# Clock_Display.net
KiCad netlist of a schematic drawn in EAGLE
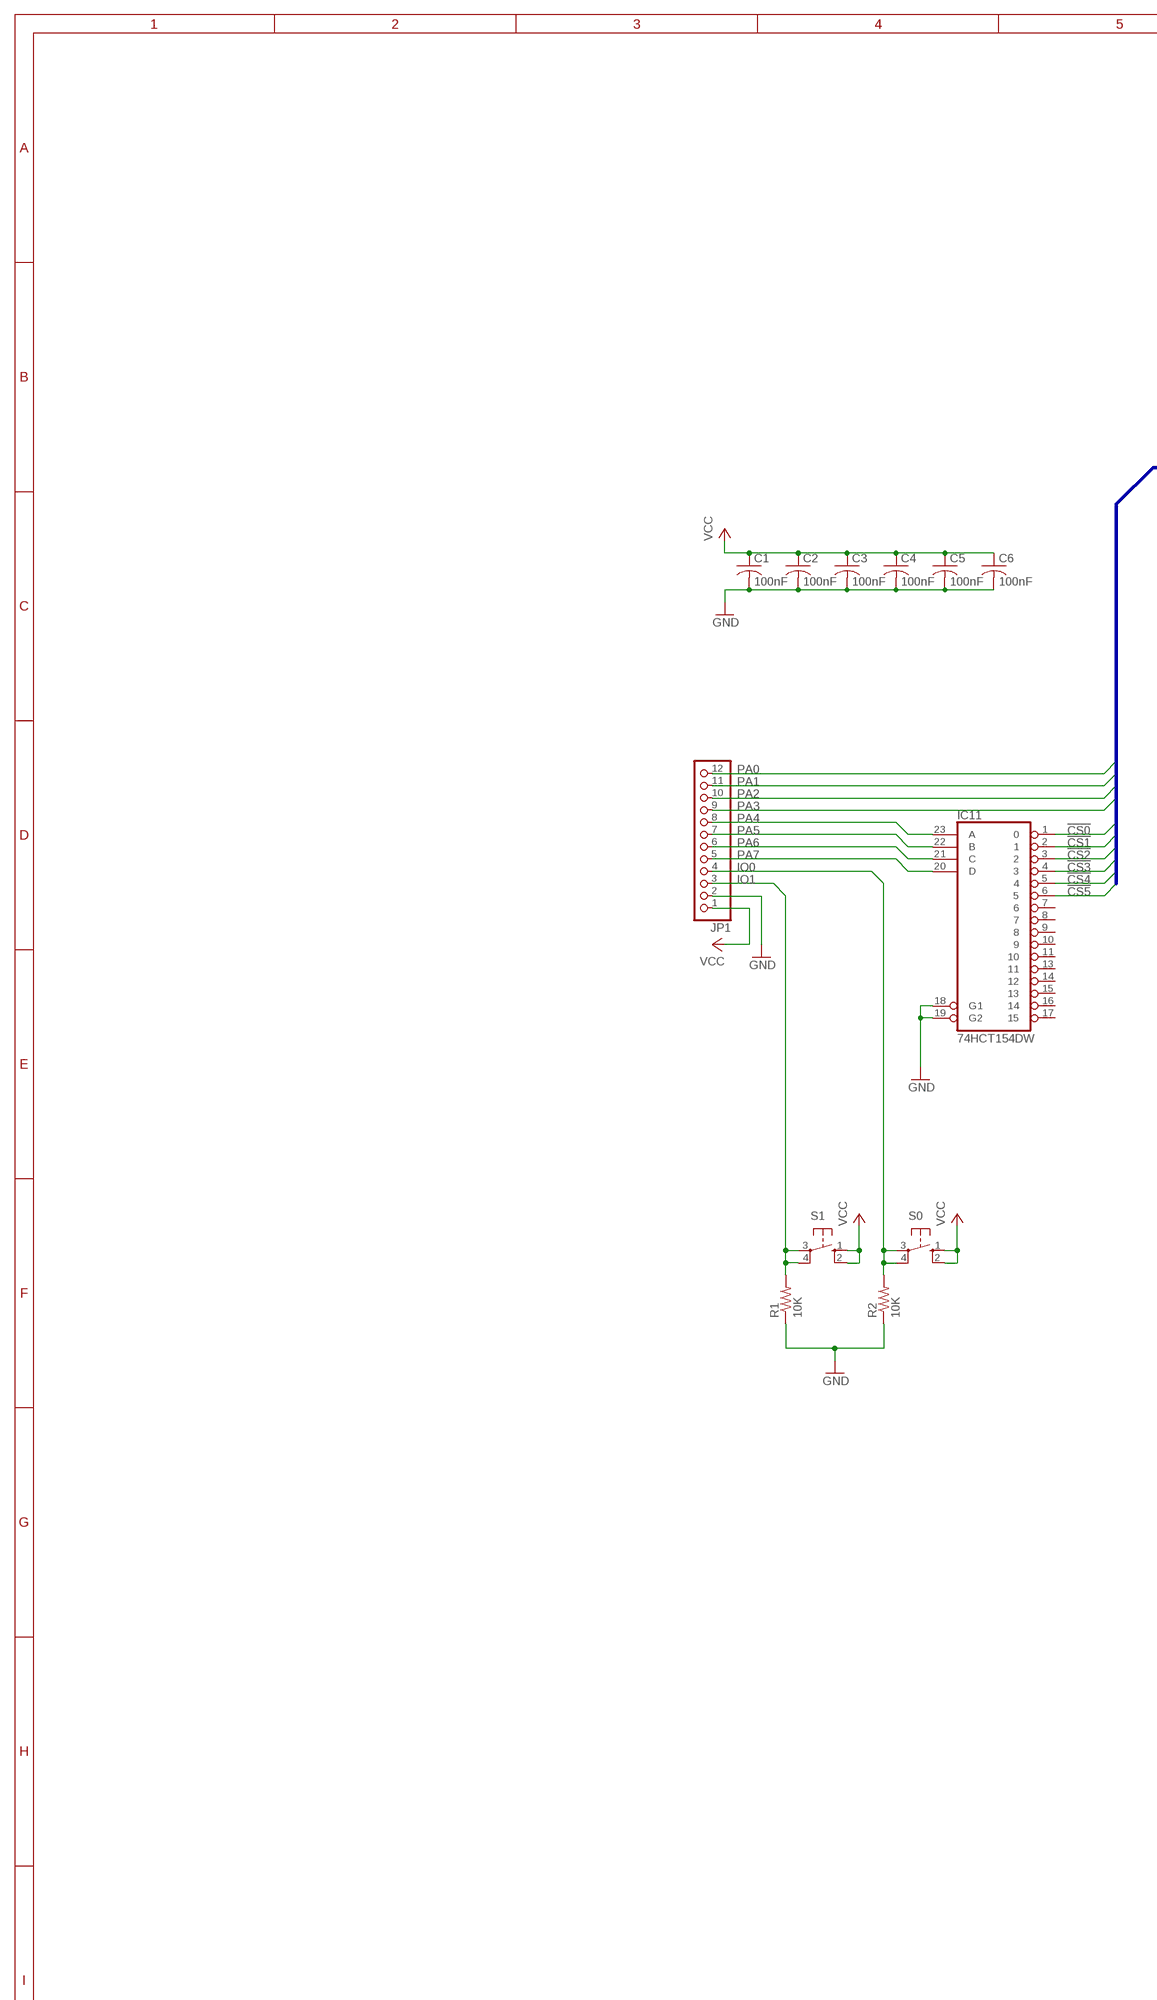
[diagram p0: schematic, sheet 1, part 1 of 2]
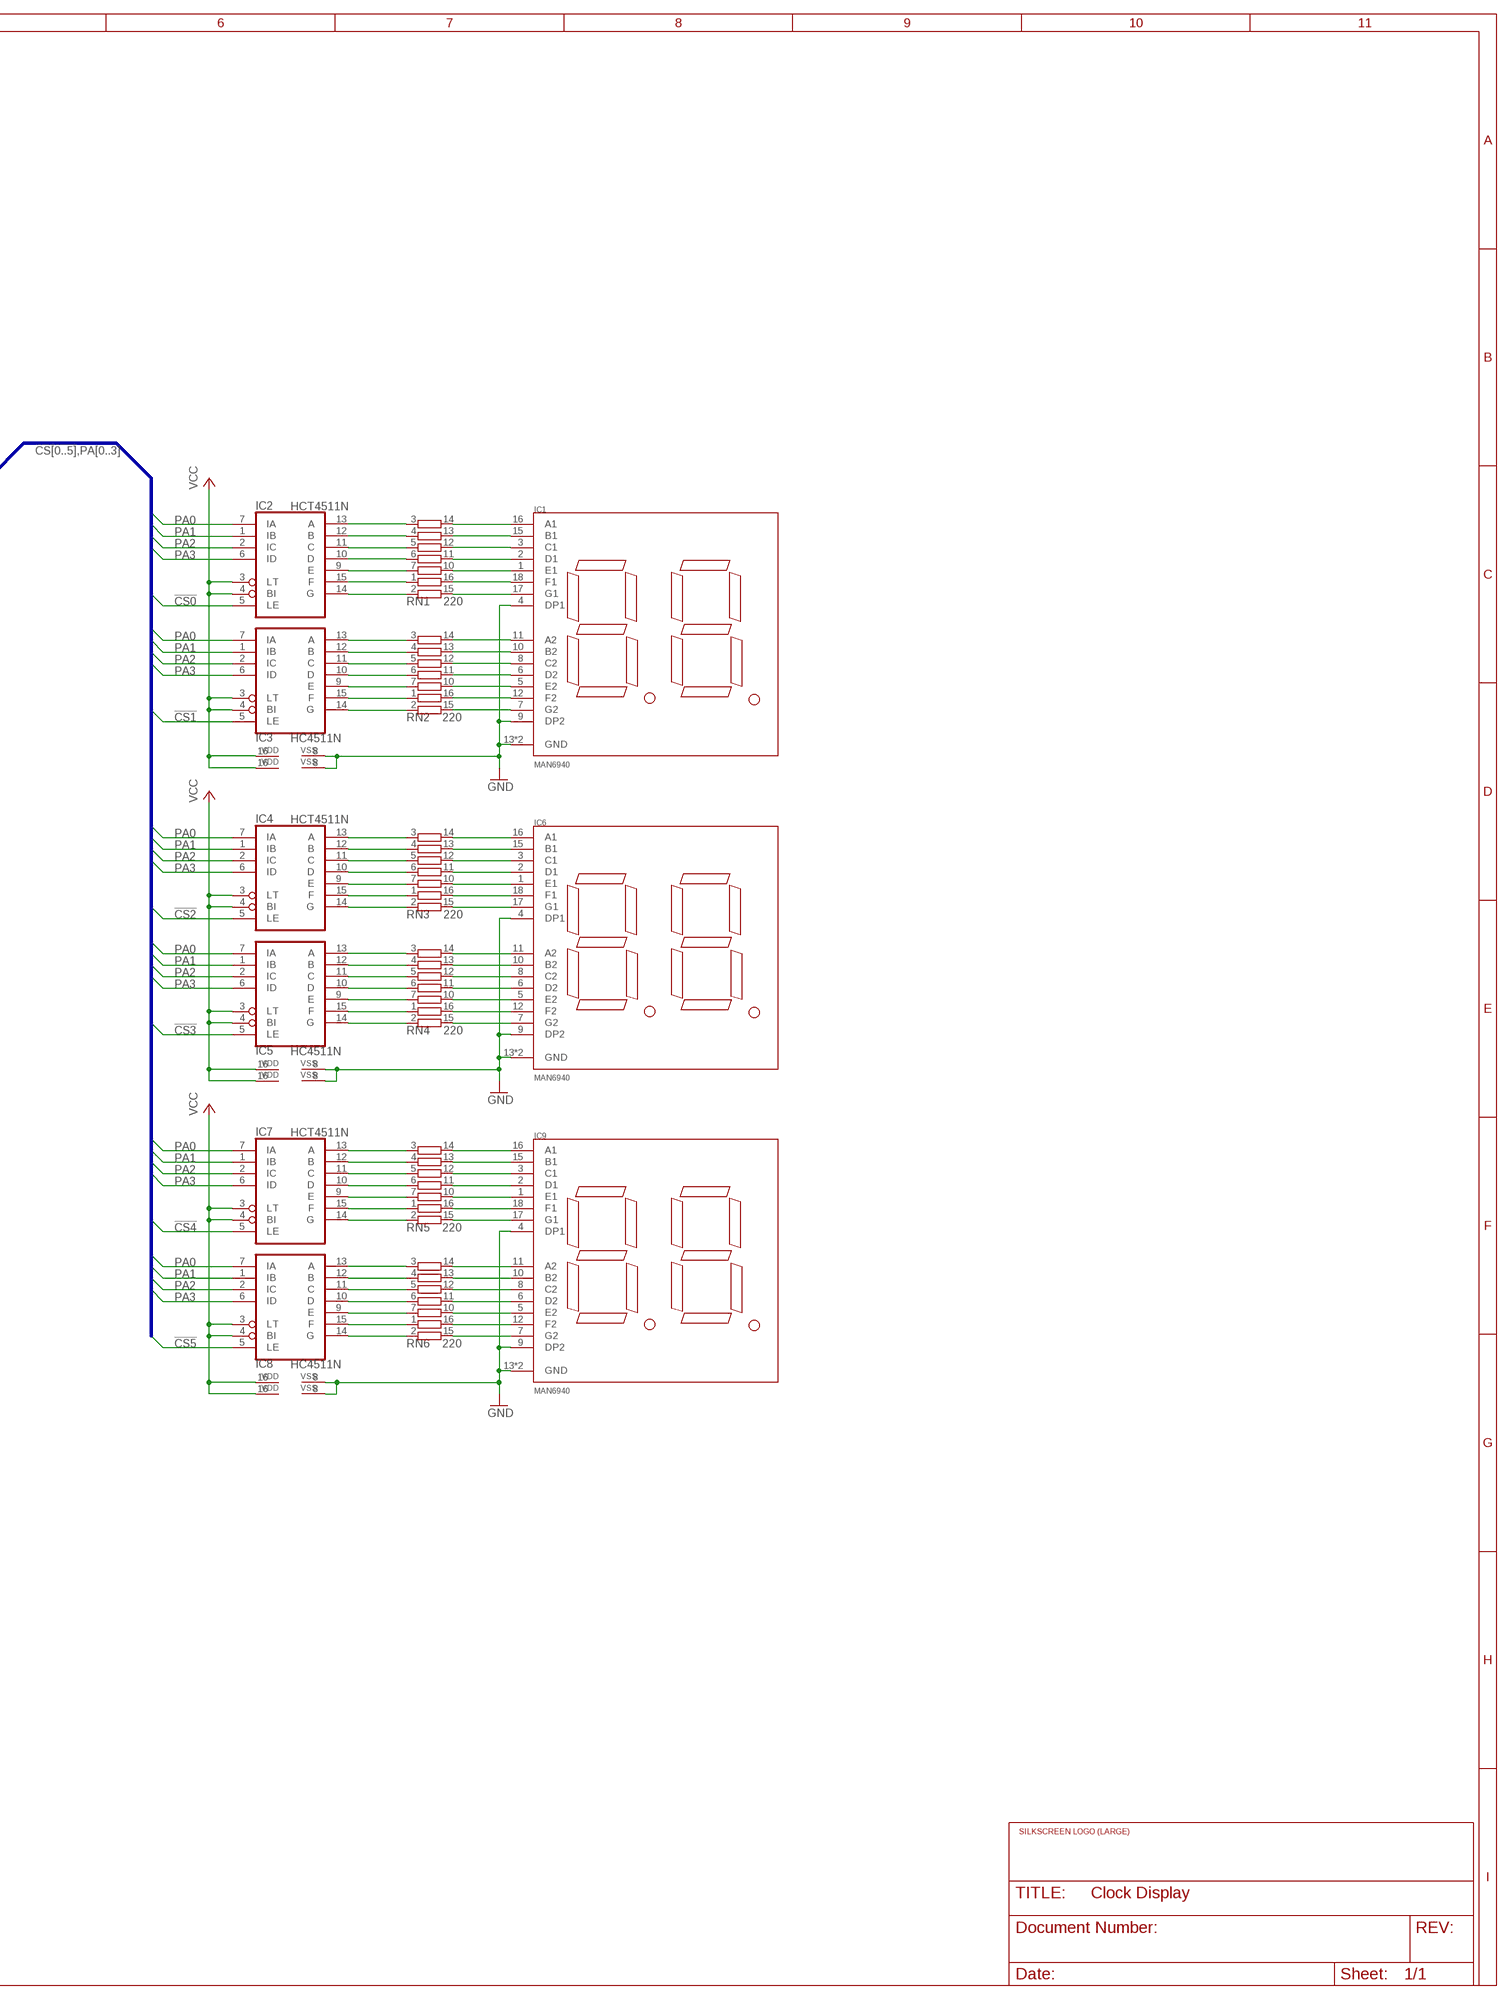
[diagram p1: schematic, sheet 1, part 2 of 2]

(export (version "E")
  (design (tool "Eeschema 10.0.6"))
  (components
    (comp (ref "C1")
      (value "100nF")
      (footprint "eagle-import:C0805")
      (libsource (lib "eagle-import") (part "C-USC0805"))
    )
    (comp (ref "C2")
      (value "100nF")
      (footprint "eagle-import:C0805")
      (libsource (lib "eagle-import") (part "C-USC0805"))
    )
    (comp (ref "C3")
      (value "100nF")
      (footprint "eagle-import:C0805")
      (libsource (lib "eagle-import") (part "C-USC0805"))
    )
    (comp (ref "C4")
      (value "100nF")
      (footprint "eagle-import:C0805")
      (libsource (lib "eagle-import") (part "C-USC0805"))
    )
    (comp (ref "C5")
      (value "100nF")
      (footprint "eagle-import:C0805")
      (libsource (lib "eagle-import") (part "C-USC0805"))
    )
    (comp (ref "C6")
      (value "100nF")
      (footprint "eagle-import:C0805")
      (libsource (lib "eagle-import") (part "C-USC0805"))
    )
    (comp (ref "IC1")
      (value "MAN6940")
      (footprint "eagle-import:MAN6940")
      (libsource (lib "eagle-import") (part "MAN6940"))
    )
    (comp (ref "IC2")
      (value "HCT4511N")
      (footprint "eagle-import:SO16")
      (libsource (lib "eagle-import") (part "4511D"))
    )
    (comp (ref "IC3")
      (value "HC4511N")
      (footprint "eagle-import:SO16")
      (libsource (lib "eagle-import") (part "4511D"))
    )
    (comp (ref "IC4")
      (value "HCT4511N")
      (footprint "eagle-import:SO16")
      (libsource (lib "eagle-import") (part "4511D"))
    )
    (comp (ref "IC5")
      (value "HC4511N")
      (footprint "eagle-import:SO16")
      (libsource (lib "eagle-import") (part "4511D"))
    )
    (comp (ref "IC6")
      (value "MAN6940")
      (footprint "eagle-import:MAN6940")
      (libsource (lib "eagle-import") (part "MAN6940"))
    )
    (comp (ref "IC7")
      (value "HCT4511N")
      (footprint "eagle-import:SO16")
      (libsource (lib "eagle-import") (part "4511D"))
    )
    (comp (ref "IC8")
      (value "HC4511N")
      (footprint "eagle-import:SO16")
      (libsource (lib "eagle-import") (part "4511D"))
    )
    (comp (ref "IC9")
      (value "MAN6940")
      (footprint "eagle-import:MAN6940")
      (libsource (lib "eagle-import") (part "MAN6940"))
    )
    (comp (ref "IC11")
      (value "74HCT154DW")
      (footprint "eagle-import:SO24W")
      (libsource (lib "eagle-import") (part "74154DWHCT"))
    )
    (comp (ref "JP1")
      (value "PINHD-1X12-CB")
      (footprint "eagle-import:1X12-CB")
      (libsource (lib "eagle-import") (part "PINHD-1X12-CB"))
    )
    (comp (ref "R1")
      (value "10K")
      (footprint "eagle-import:R0805")
      (libsource (lib "eagle-import") (part "R-US_R0805"))
    )
    (comp (ref "R2")
      (value "10K")
      (footprint "eagle-import:R0805")
      (libsource (lib "eagle-import") (part "R-US_R0805"))
    )
    (comp (ref "RN1")
      (value "220")
      (footprint "eagle-import:SOMC16")
      (libsource (lib "eagle-import") (part "8R-NSOMC"))
    )
    (comp (ref "RN2")
      (value "220")
      (footprint "eagle-import:SOMC16")
      (libsource (lib "eagle-import") (part "8R-NSOMC"))
    )
    (comp (ref "RN3")
      (value "220")
      (footprint "eagle-import:SOMC16")
      (libsource (lib "eagle-import") (part "8R-NSOMC"))
    )
    (comp (ref "RN4")
      (value "220")
      (footprint "eagle-import:SOMC16")
      (libsource (lib "eagle-import") (part "8R-NSOMC"))
    )
    (comp (ref "RN5")
      (value "220")
      (footprint "eagle-import:SOMC16")
      (libsource (lib "eagle-import") (part "8R-NSOMC"))
    )
    (comp (ref "RN6")
      (value "220")
      (footprint "eagle-import:SOMC16")
      (libsource (lib "eagle-import") (part "8R-NSOMC"))
    )
    (comp (ref "S0")
      (value "10-XX")
      (footprint "eagle-import:B3F-10XX")
      (fields (field (name "MPN") "B3F-1000"))
      (libsource (lib "eagle-import") (part "10-XX"))
    )
    (comp (ref "S1")
      (value "10-XX")
      (footprint "eagle-import:B3F-10XX")
      (fields (field (name "MPN") "B3F-1000"))
      (libsource (lib "eagle-import") (part "10-XX"))
    )
    (comp (ref "U$1")
      (value "LOGO_LARGE")
      (footprint "eagle-import:LOGO_LARGE")
      (libsource (lib "eagle-import") (part "LOGO_LARGE"))
    )
  )
  (nets
    (net (code "1") (name "/IO0") (class "Default")
      (node (ref "JP1") (pin "4") (pinfunction "4_4") (pintype "passive"))
      (node (ref "R2") (pin "2") (pinfunction "2_2") (pintype "passive"))
      (node (ref "S0") (pin "3") (pinfunction "P_3") (pintype "passive"))
      (node (ref "S0") (pin "4") (pinfunction "P1_4") (pintype "passive"))
    )
    (net (code "2") (name "/IO1") (class "Default")
      (node (ref "JP1") (pin "3") (pinfunction "3_3") (pintype "passive"))
      (node (ref "R1") (pin "2") (pinfunction "2_2") (pintype "passive"))
      (node (ref "S1") (pin "3") (pinfunction "P_3") (pintype "passive"))
      (node (ref "S1") (pin "4") (pinfunction "P1_4") (pintype "passive"))
    )
    (net (code "3") (name "/PA0") (class "Default")
      (node (ref "IC2") (pin "7") (pinfunction "IA_7") (pintype "input"))
      (node (ref "IC3") (pin "7") (pinfunction "IA_7") (pintype "input"))
      (node (ref "IC4") (pin "7") (pinfunction "IA_7") (pintype "input"))
      (node (ref "IC5") (pin "7") (pinfunction "IA_7") (pintype "input"))
      (node (ref "IC7") (pin "7") (pinfunction "IA_7") (pintype "input"))
      (node (ref "IC8") (pin "7") (pinfunction "IA_7") (pintype "input"))
      (node (ref "JP1") (pin "12") (pinfunction "12_12") (pintype "passive"))
    )
    (net (code "4") (name "/PA1") (class "Default")
      (node (ref "IC2") (pin "1") (pinfunction "IB_1") (pintype "input"))
      (node (ref "IC3") (pin "1") (pinfunction "IB_1") (pintype "input"))
      (node (ref "IC4") (pin "1") (pinfunction "IB_1") (pintype "input"))
      (node (ref "IC5") (pin "1") (pinfunction "IB_1") (pintype "input"))
      (node (ref "IC7") (pin "1") (pinfunction "IB_1") (pintype "input"))
      (node (ref "IC8") (pin "1") (pinfunction "IB_1") (pintype "input"))
      (node (ref "JP1") (pin "11") (pinfunction "11_11") (pintype "passive"))
    )
    (net (code "5") (name "/PA2") (class "Default")
      (node (ref "IC2") (pin "2") (pinfunction "IC_2") (pintype "input"))
      (node (ref "IC3") (pin "2") (pinfunction "IC_2") (pintype "input"))
      (node (ref "IC4") (pin "2") (pinfunction "IC_2") (pintype "input"))
      (node (ref "IC5") (pin "2") (pinfunction "IC_2") (pintype "input"))
      (node (ref "IC7") (pin "2") (pinfunction "IC_2") (pintype "input"))
      (node (ref "IC8") (pin "2") (pinfunction "IC_2") (pintype "input"))
      (node (ref "JP1") (pin "10") (pinfunction "10_10") (pintype "passive"))
    )
    (net (code "6") (name "/PA3") (class "Default")
      (node (ref "IC2") (pin "6") (pinfunction "ID_6") (pintype "input"))
      (node (ref "IC3") (pin "6") (pinfunction "ID_6") (pintype "input"))
      (node (ref "IC4") (pin "6") (pinfunction "ID_6") (pintype "input"))
      (node (ref "IC5") (pin "6") (pinfunction "ID_6") (pintype "input"))
      (node (ref "IC7") (pin "6") (pinfunction "ID_6") (pintype "input"))
      (node (ref "IC8") (pin "6") (pinfunction "ID_6") (pintype "input"))
      (node (ref "JP1") (pin "9") (pinfunction "9_9") (pintype "passive"))
    )
    (net (code "7") (name "/PA4") (class "Default")
      (node (ref "IC11") (pin "23") (pinfunction "A_23") (pintype "input"))
      (node (ref "JP1") (pin "8") (pinfunction "8_8") (pintype "passive"))
    )
    (net (code "8") (name "/PA5") (class "Default")
      (node (ref "IC11") (pin "22") (pinfunction "B_22") (pintype "input"))
      (node (ref "JP1") (pin "7") (pinfunction "7_7") (pintype "passive"))
    )
    (net (code "9") (name "/PA6") (class "Default")
      (node (ref "IC11") (pin "21") (pinfunction "C_21") (pintype "input"))
      (node (ref "JP1") (pin "6") (pinfunction "6_6") (pintype "passive"))
    )
    (net (code "10") (name "/PA7") (class "Default")
      (node (ref "IC11") (pin "20") (pinfunction "D_20") (pintype "input"))
      (node (ref "JP1") (pin "5") (pinfunction "5_5") (pintype "passive"))
    )
    (net (code "12") (name "/~{CS0}") (class "Default")
      (node (ref "IC11") (pin "1") (pinfunction "0_1") (pintype "output"))
      (node (ref "IC2") (pin "5") (pinfunction "LE_5") (pintype "input"))
    )
    (net (code "13") (name "/~{CS1}") (class "Default")
      (node (ref "IC11") (pin "2") (pinfunction "1_2") (pintype "output"))
      (node (ref "IC3") (pin "5") (pinfunction "LE_5") (pintype "input"))
    )
    (net (code "14") (name "/~{CS2}") (class "Default")
      (node (ref "IC11") (pin "3") (pinfunction "2_3") (pintype "output"))
      (node (ref "IC4") (pin "5") (pinfunction "LE_5") (pintype "input"))
    )
    (net (code "15") (name "/~{CS3}") (class "Default")
      (node (ref "IC11") (pin "4") (pinfunction "3_4") (pintype "output"))
      (node (ref "IC5") (pin "5") (pinfunction "LE_5") (pintype "input"))
    )
    (net (code "16") (name "/~{CS4}") (class "Default")
      (node (ref "IC11") (pin "5") (pinfunction "4_5") (pintype "output"))
      (node (ref "IC7") (pin "5") (pinfunction "LE_5") (pintype "input"))
    )
    (net (code "17") (name "/~{CS5}") (class "Default")
      (node (ref "IC11") (pin "6") (pinfunction "5_6") (pintype "output"))
      (node (ref "IC8") (pin "5") (pinfunction "LE_5") (pintype "input"))
    )
    (net (code "18") (name "GND") (class "Default")
      (node (ref "C1") (pin "2") (pinfunction "2_2") (pintype "passive"))
      (node (ref "C2") (pin "2") (pinfunction "2_2") (pintype "passive"))
      (node (ref "C3") (pin "2") (pinfunction "2_2") (pintype "passive"))
      (node (ref "C4") (pin "2") (pinfunction "2_2") (pintype "passive"))
      (node (ref "C5") (pin "2") (pinfunction "2_2") (pintype "passive"))
      (node (ref "C6") (pin "2") (pinfunction "2_2") (pintype "passive"))
      (node (ref "IC1") (pin "13") (pinfunction "GND_13") (pintype "power_in"))
      (node (ref "IC1") (pin "14") (pinfunction "GND_14") (pintype "power_in"))
      (node (ref "IC1") (pin "4") (pinfunction "DP1_4") (pintype "input"))
      (node (ref "IC1") (pin "9") (pinfunction "DP2_9") (pintype "input"))
      (node (ref "IC11") (pin "18") (pinfunction "G1_18") (pintype "input"))
      (node (ref "IC11") (pin "19") (pinfunction "G2_19") (pintype "input"))
      (node (ref "IC2") (pin "8") (pinfunction "VSS_8") (pintype "power_in"))
      (node (ref "IC3") (pin "8") (pinfunction "VSS_8") (pintype "power_in"))
      (node (ref "IC4") (pin "8") (pinfunction "VSS_8") (pintype "power_in"))
      (node (ref "IC5") (pin "8") (pinfunction "VSS_8") (pintype "power_in"))
      (node (ref "IC6") (pin "13") (pinfunction "GND_13") (pintype "power_in"))
      (node (ref "IC6") (pin "14") (pinfunction "GND_14") (pintype "power_in"))
      (node (ref "IC6") (pin "4") (pinfunction "DP1_4") (pintype "input"))
      (node (ref "IC6") (pin "9") (pinfunction "DP2_9") (pintype "input"))
      (node (ref "IC7") (pin "8") (pinfunction "VSS_8") (pintype "power_in"))
      (node (ref "IC8") (pin "8") (pinfunction "VSS_8") (pintype "power_in"))
      (node (ref "IC9") (pin "13") (pinfunction "GND_13") (pintype "power_in"))
      (node (ref "IC9") (pin "14") (pinfunction "GND_14") (pintype "power_in"))
      (node (ref "IC9") (pin "4") (pinfunction "DP1_4") (pintype "input"))
      (node (ref "IC9") (pin "9") (pinfunction "DP2_9") (pintype "input"))
      (node (ref "JP1") (pin "2") (pinfunction "2_2") (pintype "passive"))
      (node (ref "R1") (pin "1") (pinfunction "1_1") (pintype "passive"))
      (node (ref "R2") (pin "1") (pinfunction "1_1") (pintype "passive"))
    )
    (net (code "19") (name "Net-(IC1-A1)") (class "Default")
      (node (ref "IC1") (pin "16") (pinfunction "A1_16") (pintype "input"))
      (node (ref "RN1") (pin "14") (pinfunction "2_14") (pintype "passive"))
    )
    (net (code "20") (name "Net-(IC1-A2)") (class "Default")
      (node (ref "IC1") (pin "11") (pinfunction "A2_11") (pintype "input"))
      (node (ref "RN2") (pin "14") (pinfunction "2_14") (pintype "passive"))
    )
    (net (code "21") (name "Net-(IC1-B1)") (class "Default")
      (node (ref "IC1") (pin "15") (pinfunction "B1_15") (pintype "input"))
      (node (ref "RN1") (pin "13") (pinfunction "2_13") (pintype "passive"))
    )
    (net (code "22") (name "Net-(IC1-B2)") (class "Default")
      (node (ref "IC1") (pin "10") (pinfunction "B2_10") (pintype "input"))
      (node (ref "RN2") (pin "13") (pinfunction "2_13") (pintype "passive"))
    )
    (net (code "23") (name "Net-(IC1-C1)") (class "Default")
      (node (ref "IC1") (pin "3") (pinfunction "C1_3") (pintype "input"))
      (node (ref "RN1") (pin "12") (pinfunction "2_12") (pintype "passive"))
    )
    (net (code "24") (name "Net-(IC1-C2)") (class "Default")
      (node (ref "IC1") (pin "8") (pinfunction "C2_8") (pintype "input"))
      (node (ref "RN2") (pin "12") (pinfunction "2_12") (pintype "passive"))
    )
    (net (code "25") (name "Net-(IC1-D1)") (class "Default")
      (node (ref "IC1") (pin "2") (pinfunction "D1_2") (pintype "input"))
      (node (ref "RN1") (pin "11") (pinfunction "2_11") (pintype "passive"))
    )
    (net (code "26") (name "Net-(IC1-D2)") (class "Default")
      (node (ref "IC1") (pin "6") (pinfunction "D2_6") (pintype "input"))
      (node (ref "RN2") (pin "11") (pinfunction "2_11") (pintype "passive"))
    )
    (net (code "27") (name "Net-(IC1-E1)") (class "Default")
      (node (ref "IC1") (pin "1") (pinfunction "E1_1") (pintype "input"))
      (node (ref "RN1") (pin "10") (pinfunction "2_10") (pintype "passive"))
    )
    (net (code "28") (name "Net-(IC1-E2)") (class "Default")
      (node (ref "IC1") (pin "5") (pinfunction "E2_5") (pintype "input"))
      (node (ref "RN2") (pin "10") (pinfunction "2_10") (pintype "passive"))
    )
    (net (code "29") (name "Net-(IC1-F1)") (class "Default")
      (node (ref "IC1") (pin "18") (pinfunction "F1_18") (pintype "input"))
      (node (ref "RN1") (pin "16") (pinfunction "2_16") (pintype "passive"))
    )
    (net (code "30") (name "Net-(IC1-F2)") (class "Default")
      (node (ref "IC1") (pin "12") (pinfunction "F2_12") (pintype "input"))
      (node (ref "RN2") (pin "16") (pinfunction "2_16") (pintype "passive"))
    )
    (net (code "31") (name "Net-(IC1-G1)") (class "Default")
      (node (ref "IC1") (pin "17") (pinfunction "G1_17") (pintype "input"))
      (node (ref "RN1") (pin "15") (pinfunction "2_15") (pintype "passive"))
    )
    (net (code "32") (name "Net-(IC1-G2)") (class "Default")
      (node (ref "IC1") (pin "7") (pinfunction "G2_7") (pintype "input"))
      (node (ref "RN2") (pin "15") (pinfunction "2_15") (pintype "passive"))
    )
    (net (code "33") (name "Net-(IC2A-A)") (class "Default")
      (node (ref "IC2") (pin "13") (pinfunction "A_13") (pintype "output"))
      (node (ref "RN1") (pin "3") (pinfunction "1_3") (pintype "passive"))
    )
    (net (code "34") (name "Net-(IC2A-B)") (class "Default")
      (node (ref "IC2") (pin "12") (pinfunction "B_12") (pintype "output"))
      (node (ref "RN1") (pin "4") (pinfunction "1_4") (pintype "passive"))
    )
    (net (code "35") (name "Net-(IC2A-C)") (class "Default")
      (node (ref "IC2") (pin "11") (pinfunction "C_11") (pintype "output"))
      (node (ref "RN1") (pin "5") (pinfunction "1_5") (pintype "passive"))
    )
    (net (code "36") (name "Net-(IC2A-D)") (class "Default")
      (node (ref "IC2") (pin "10") (pinfunction "D_10") (pintype "output"))
      (node (ref "RN1") (pin "6") (pinfunction "1_6") (pintype "passive"))
    )
    (net (code "37") (name "Net-(IC2A-E)") (class "Default")
      (node (ref "IC2") (pin "9") (pinfunction "E_9") (pintype "output"))
      (node (ref "RN1") (pin "7") (pinfunction "1_7") (pintype "passive"))
    )
    (net (code "38") (name "Net-(IC2A-F)") (class "Default")
      (node (ref "IC2") (pin "15") (pinfunction "F_15") (pintype "output"))
      (node (ref "RN1") (pin "1") (pinfunction "1_1") (pintype "passive"))
    )
    (net (code "39") (name "Net-(IC2A-G)") (class "Default")
      (node (ref "IC2") (pin "14") (pinfunction "G_14") (pintype "output"))
      (node (ref "RN1") (pin "2") (pinfunction "1_2") (pintype "passive"))
    )
    (net (code "40") (name "Net-(IC3A-A)") (class "Default")
      (node (ref "IC3") (pin "13") (pinfunction "A_13") (pintype "output"))
      (node (ref "RN2") (pin "3") (pinfunction "1_3") (pintype "passive"))
    )
    (net (code "41") (name "Net-(IC3A-B)") (class "Default")
      (node (ref "IC3") (pin "12") (pinfunction "B_12") (pintype "output"))
      (node (ref "RN2") (pin "4") (pinfunction "1_4") (pintype "passive"))
    )
    (net (code "42") (name "Net-(IC3A-C)") (class "Default")
      (node (ref "IC3") (pin "11") (pinfunction "C_11") (pintype "output"))
      (node (ref "RN2") (pin "5") (pinfunction "1_5") (pintype "passive"))
    )
    (net (code "43") (name "Net-(IC3A-D)") (class "Default")
      (node (ref "IC3") (pin "10") (pinfunction "D_10") (pintype "output"))
      (node (ref "RN2") (pin "6") (pinfunction "1_6") (pintype "passive"))
    )
    (net (code "44") (name "Net-(IC3A-E)") (class "Default")
      (node (ref "IC3") (pin "9") (pinfunction "E_9") (pintype "output"))
      (node (ref "RN2") (pin "7") (pinfunction "1_7") (pintype "passive"))
    )
    (net (code "45") (name "Net-(IC3A-F)") (class "Default")
      (node (ref "IC3") (pin "15") (pinfunction "F_15") (pintype "output"))
      (node (ref "RN2") (pin "1") (pinfunction "1_1") (pintype "passive"))
    )
    (net (code "46") (name "Net-(IC3A-G)") (class "Default")
      (node (ref "IC3") (pin "14") (pinfunction "G_14") (pintype "output"))
      (node (ref "RN2") (pin "2") (pinfunction "1_2") (pintype "passive"))
    )
    (net (code "47") (name "Net-(IC4A-A)") (class "Default")
      (node (ref "IC4") (pin "13") (pinfunction "A_13") (pintype "output"))
      (node (ref "RN3") (pin "3") (pinfunction "1_3") (pintype "passive"))
    )
    (net (code "48") (name "Net-(IC4A-B)") (class "Default")
      (node (ref "IC4") (pin "12") (pinfunction "B_12") (pintype "output"))
      (node (ref "RN3") (pin "4") (pinfunction "1_4") (pintype "passive"))
    )
    (net (code "49") (name "Net-(IC4A-C)") (class "Default")
      (node (ref "IC4") (pin "11") (pinfunction "C_11") (pintype "output"))
      (node (ref "RN3") (pin "5") (pinfunction "1_5") (pintype "passive"))
    )
    (net (code "50") (name "Net-(IC4A-D)") (class "Default")
      (node (ref "IC4") (pin "10") (pinfunction "D_10") (pintype "output"))
      (node (ref "RN3") (pin "6") (pinfunction "1_6") (pintype "passive"))
    )
    (net (code "51") (name "Net-(IC4A-E)") (class "Default")
      (node (ref "IC4") (pin "9") (pinfunction "E_9") (pintype "output"))
      (node (ref "RN3") (pin "7") (pinfunction "1_7") (pintype "passive"))
    )
    (net (code "52") (name "Net-(IC4A-F)") (class "Default")
      (node (ref "IC4") (pin "15") (pinfunction "F_15") (pintype "output"))
      (node (ref "RN3") (pin "1") (pinfunction "1_1") (pintype "passive"))
    )
    (net (code "53") (name "Net-(IC4A-G)") (class "Default")
      (node (ref "IC4") (pin "14") (pinfunction "G_14") (pintype "output"))
      (node (ref "RN3") (pin "2") (pinfunction "1_2") (pintype "passive"))
    )
    (net (code "54") (name "Net-(IC5A-A)") (class "Default")
      (node (ref "IC5") (pin "13") (pinfunction "A_13") (pintype "output"))
      (node (ref "RN4") (pin "3") (pinfunction "1_3") (pintype "passive"))
    )
    (net (code "55") (name "Net-(IC5A-B)") (class "Default")
      (node (ref "IC5") (pin "12") (pinfunction "B_12") (pintype "output"))
      (node (ref "RN4") (pin "4") (pinfunction "1_4") (pintype "passive"))
    )
    (net (code "56") (name "Net-(IC5A-C)") (class "Default")
      (node (ref "IC5") (pin "11") (pinfunction "C_11") (pintype "output"))
      (node (ref "RN4") (pin "5") (pinfunction "1_5") (pintype "passive"))
    )
    (net (code "57") (name "Net-(IC5A-D)") (class "Default")
      (node (ref "IC5") (pin "10") (pinfunction "D_10") (pintype "output"))
      (node (ref "RN4") (pin "6") (pinfunction "1_6") (pintype "passive"))
    )
    (net (code "58") (name "Net-(IC5A-E)") (class "Default")
      (node (ref "IC5") (pin "9") (pinfunction "E_9") (pintype "output"))
      (node (ref "RN4") (pin "7") (pinfunction "1_7") (pintype "passive"))
    )
    (net (code "59") (name "Net-(IC5A-F)") (class "Default")
      (node (ref "IC5") (pin "15") (pinfunction "F_15") (pintype "output"))
      (node (ref "RN4") (pin "1") (pinfunction "1_1") (pintype "passive"))
    )
    (net (code "60") (name "Net-(IC5A-G)") (class "Default")
      (node (ref "IC5") (pin "14") (pinfunction "G_14") (pintype "output"))
      (node (ref "RN4") (pin "2") (pinfunction "1_2") (pintype "passive"))
    )
    (net (code "61") (name "Net-(IC6-A1)") (class "Default")
      (node (ref "IC6") (pin "16") (pinfunction "A1_16") (pintype "input"))
      (node (ref "RN3") (pin "14") (pinfunction "2_14") (pintype "passive"))
    )
    (net (code "62") (name "Net-(IC6-A2)") (class "Default")
      (node (ref "IC6") (pin "11") (pinfunction "A2_11") (pintype "input"))
      (node (ref "RN4") (pin "14") (pinfunction "2_14") (pintype "passive"))
    )
    (net (code "63") (name "Net-(IC6-B1)") (class "Default")
      (node (ref "IC6") (pin "15") (pinfunction "B1_15") (pintype "input"))
      (node (ref "RN3") (pin "13") (pinfunction "2_13") (pintype "passive"))
    )
    (net (code "64") (name "Net-(IC6-B2)") (class "Default")
      (node (ref "IC6") (pin "10") (pinfunction "B2_10") (pintype "input"))
      (node (ref "RN4") (pin "13") (pinfunction "2_13") (pintype "passive"))
    )
    (net (code "65") (name "Net-(IC6-C1)") (class "Default")
      (node (ref "IC6") (pin "3") (pinfunction "C1_3") (pintype "input"))
      (node (ref "RN3") (pin "12") (pinfunction "2_12") (pintype "passive"))
    )
    (net (code "66") (name "Net-(IC6-C2)") (class "Default")
      (node (ref "IC6") (pin "8") (pinfunction "C2_8") (pintype "input"))
      (node (ref "RN4") (pin "12") (pinfunction "2_12") (pintype "passive"))
    )
    (net (code "67") (name "Net-(IC6-D1)") (class "Default")
      (node (ref "IC6") (pin "2") (pinfunction "D1_2") (pintype "input"))
      (node (ref "RN3") (pin "11") (pinfunction "2_11") (pintype "passive"))
    )
    (net (code "68") (name "Net-(IC6-D2)") (class "Default")
      (node (ref "IC6") (pin "6") (pinfunction "D2_6") (pintype "input"))
      (node (ref "RN4") (pin "11") (pinfunction "2_11") (pintype "passive"))
    )
    (net (code "69") (name "Net-(IC6-E1)") (class "Default")
      (node (ref "IC6") (pin "1") (pinfunction "E1_1") (pintype "input"))
      (node (ref "RN3") (pin "10") (pinfunction "2_10") (pintype "passive"))
    )
    (net (code "70") (name "Net-(IC6-E2)") (class "Default")
      (node (ref "IC6") (pin "5") (pinfunction "E2_5") (pintype "input"))
      (node (ref "RN4") (pin "10") (pinfunction "2_10") (pintype "passive"))
    )
    (net (code "71") (name "Net-(IC6-F1)") (class "Default")
      (node (ref "IC6") (pin "18") (pinfunction "F1_18") (pintype "input"))
      (node (ref "RN3") (pin "16") (pinfunction "2_16") (pintype "passive"))
    )
    (net (code "72") (name "Net-(IC6-F2)") (class "Default")
      (node (ref "IC6") (pin "12") (pinfunction "F2_12") (pintype "input"))
      (node (ref "RN4") (pin "16") (pinfunction "2_16") (pintype "passive"))
    )
    (net (code "73") (name "Net-(IC6-G1)") (class "Default")
      (node (ref "IC6") (pin "17") (pinfunction "G1_17") (pintype "input"))
      (node (ref "RN3") (pin "15") (pinfunction "2_15") (pintype "passive"))
    )
    (net (code "74") (name "Net-(IC6-G2)") (class "Default")
      (node (ref "IC6") (pin "7") (pinfunction "G2_7") (pintype "input"))
      (node (ref "RN4") (pin "15") (pinfunction "2_15") (pintype "passive"))
    )
    (net (code "75") (name "Net-(IC7A-A)") (class "Default")
      (node (ref "IC7") (pin "13") (pinfunction "A_13") (pintype "output"))
      (node (ref "RN5") (pin "3") (pinfunction "1_3") (pintype "passive"))
    )
    (net (code "76") (name "Net-(IC7A-B)") (class "Default")
      (node (ref "IC7") (pin "12") (pinfunction "B_12") (pintype "output"))
      (node (ref "RN5") (pin "4") (pinfunction "1_4") (pintype "passive"))
    )
    (net (code "77") (name "Net-(IC7A-C)") (class "Default")
      (node (ref "IC7") (pin "11") (pinfunction "C_11") (pintype "output"))
      (node (ref "RN5") (pin "5") (pinfunction "1_5") (pintype "passive"))
    )
    (net (code "78") (name "Net-(IC7A-D)") (class "Default")
      (node (ref "IC7") (pin "10") (pinfunction "D_10") (pintype "output"))
      (node (ref "RN5") (pin "6") (pinfunction "1_6") (pintype "passive"))
    )
    (net (code "79") (name "Net-(IC7A-E)") (class "Default")
      (node (ref "IC7") (pin "9") (pinfunction "E_9") (pintype "output"))
      (node (ref "RN5") (pin "7") (pinfunction "1_7") (pintype "passive"))
    )
    (net (code "80") (name "Net-(IC7A-F)") (class "Default")
      (node (ref "IC7") (pin "15") (pinfunction "F_15") (pintype "output"))
      (node (ref "RN5") (pin "1") (pinfunction "1_1") (pintype "passive"))
    )
    (net (code "81") (name "Net-(IC7A-G)") (class "Default")
      (node (ref "IC7") (pin "14") (pinfunction "G_14") (pintype "output"))
      (node (ref "RN5") (pin "2") (pinfunction "1_2") (pintype "passive"))
    )
    (net (code "82") (name "Net-(IC8A-A)") (class "Default")
      (node (ref "IC8") (pin "13") (pinfunction "A_13") (pintype "output"))
      (node (ref "RN6") (pin "3") (pinfunction "1_3") (pintype "passive"))
    )
    (net (code "83") (name "Net-(IC8A-B)") (class "Default")
      (node (ref "IC8") (pin "12") (pinfunction "B_12") (pintype "output"))
      (node (ref "RN6") (pin "4") (pinfunction "1_4") (pintype "passive"))
    )
    (net (code "84") (name "Net-(IC8A-C)") (class "Default")
      (node (ref "IC8") (pin "11") (pinfunction "C_11") (pintype "output"))
      (node (ref "RN6") (pin "5") (pinfunction "1_5") (pintype "passive"))
    )
    (net (code "85") (name "Net-(IC8A-D)") (class "Default")
      (node (ref "IC8") (pin "10") (pinfunction "D_10") (pintype "output"))
      (node (ref "RN6") (pin "6") (pinfunction "1_6") (pintype "passive"))
    )
    (net (code "86") (name "Net-(IC8A-E)") (class "Default")
      (node (ref "IC8") (pin "9") (pinfunction "E_9") (pintype "output"))
      (node (ref "RN6") (pin "7") (pinfunction "1_7") (pintype "passive"))
    )
    (net (code "87") (name "Net-(IC8A-F)") (class "Default")
      (node (ref "IC8") (pin "15") (pinfunction "F_15") (pintype "output"))
      (node (ref "RN6") (pin "1") (pinfunction "1_1") (pintype "passive"))
    )
    (net (code "88") (name "Net-(IC8A-G)") (class "Default")
      (node (ref "IC8") (pin "14") (pinfunction "G_14") (pintype "output"))
      (node (ref "RN6") (pin "2") (pinfunction "1_2") (pintype "passive"))
    )
    (net (code "89") (name "Net-(IC9-A1)") (class "Default")
      (node (ref "IC9") (pin "16") (pinfunction "A1_16") (pintype "input"))
      (node (ref "RN5") (pin "14") (pinfunction "2_14") (pintype "passive"))
    )
    (net (code "90") (name "Net-(IC9-A2)") (class "Default")
      (node (ref "IC9") (pin "11") (pinfunction "A2_11") (pintype "input"))
      (node (ref "RN6") (pin "14") (pinfunction "2_14") (pintype "passive"))
    )
    (net (code "91") (name "Net-(IC9-B1)") (class "Default")
      (node (ref "IC9") (pin "15") (pinfunction "B1_15") (pintype "input"))
      (node (ref "RN5") (pin "13") (pinfunction "2_13") (pintype "passive"))
    )
    (net (code "92") (name "Net-(IC9-B2)") (class "Default")
      (node (ref "IC9") (pin "10") (pinfunction "B2_10") (pintype "input"))
      (node (ref "RN6") (pin "13") (pinfunction "2_13") (pintype "passive"))
    )
    (net (code "93") (name "Net-(IC9-C1)") (class "Default")
      (node (ref "IC9") (pin "3") (pinfunction "C1_3") (pintype "input"))
      (node (ref "RN5") (pin "12") (pinfunction "2_12") (pintype "passive"))
    )
    (net (code "94") (name "Net-(IC9-C2)") (class "Default")
      (node (ref "IC9") (pin "8") (pinfunction "C2_8") (pintype "input"))
      (node (ref "RN6") (pin "12") (pinfunction "2_12") (pintype "passive"))
    )
    (net (code "95") (name "Net-(IC9-D1)") (class "Default")
      (node (ref "IC9") (pin "2") (pinfunction "D1_2") (pintype "input"))
      (node (ref "RN5") (pin "11") (pinfunction "2_11") (pintype "passive"))
    )
    (net (code "96") (name "Net-(IC9-D2)") (class "Default")
      (node (ref "IC9") (pin "6") (pinfunction "D2_6") (pintype "input"))
      (node (ref "RN6") (pin "11") (pinfunction "2_11") (pintype "passive"))
    )
    (net (code "97") (name "Net-(IC9-E1)") (class "Default")
      (node (ref "IC9") (pin "1") (pinfunction "E1_1") (pintype "input"))
      (node (ref "RN5") (pin "10") (pinfunction "2_10") (pintype "passive"))
    )
    (net (code "98") (name "Net-(IC9-E2)") (class "Default")
      (node (ref "IC9") (pin "5") (pinfunction "E2_5") (pintype "input"))
      (node (ref "RN6") (pin "10") (pinfunction "2_10") (pintype "passive"))
    )
    (net (code "99") (name "Net-(IC9-F1)") (class "Default")
      (node (ref "IC9") (pin "18") (pinfunction "F1_18") (pintype "input"))
      (node (ref "RN5") (pin "16") (pinfunction "2_16") (pintype "passive"))
    )
    (net (code "100") (name "Net-(IC9-F2)") (class "Default")
      (node (ref "IC9") (pin "12") (pinfunction "F2_12") (pintype "input"))
      (node (ref "RN6") (pin "16") (pinfunction "2_16") (pintype "passive"))
    )
    (net (code "101") (name "Net-(IC9-G1)") (class "Default")
      (node (ref "IC9") (pin "17") (pinfunction "G1_17") (pintype "input"))
      (node (ref "RN5") (pin "15") (pinfunction "2_15") (pintype "passive"))
    )
    (net (code "102") (name "Net-(IC9-G2)") (class "Default")
      (node (ref "IC9") (pin "7") (pinfunction "G2_7") (pintype "input"))
      (node (ref "RN6") (pin "15") (pinfunction "2_15") (pintype "passive"))
    )
    (net (code "103") (name "VCC") (class "Default")
      (node (ref "C1") (pin "1") (pinfunction "1_1") (pintype "passive"))
      (node (ref "C2") (pin "1") (pinfunction "1_1") (pintype "passive"))
      (node (ref "C3") (pin "1") (pinfunction "1_1") (pintype "passive"))
      (node (ref "C4") (pin "1") (pinfunction "1_1") (pintype "passive"))
      (node (ref "C5") (pin "1") (pinfunction "1_1") (pintype "passive"))
      (node (ref "C6") (pin "1") (pinfunction "1_1") (pintype "passive"))
      (node (ref "IC2") (pin "16") (pinfunction "VDD_16") (pintype "power_in"))
      (node (ref "IC2") (pin "3") (pinfunction "LT_3") (pintype "input"))
      (node (ref "IC2") (pin "4") (pinfunction "BI_4") (pintype "input"))
      (node (ref "IC3") (pin "16") (pinfunction "VDD_16") (pintype "power_in"))
      (node (ref "IC3") (pin "3") (pinfunction "LT_3") (pintype "input"))
      (node (ref "IC3") (pin "4") (pinfunction "BI_4") (pintype "input"))
      (node (ref "IC4") (pin "16") (pinfunction "VDD_16") (pintype "power_in"))
      (node (ref "IC4") (pin "3") (pinfunction "LT_3") (pintype "input"))
      (node (ref "IC4") (pin "4") (pinfunction "BI_4") (pintype "input"))
      (node (ref "IC5") (pin "16") (pinfunction "VDD_16") (pintype "power_in"))
      (node (ref "IC5") (pin "3") (pinfunction "LT_3") (pintype "input"))
      (node (ref "IC5") (pin "4") (pinfunction "BI_4") (pintype "input"))
      (node (ref "IC7") (pin "16") (pinfunction "VDD_16") (pintype "power_in"))
      (node (ref "IC7") (pin "3") (pinfunction "LT_3") (pintype "input"))
      (node (ref "IC7") (pin "4") (pinfunction "BI_4") (pintype "input"))
      (node (ref "IC8") (pin "16") (pinfunction "VDD_16") (pintype "power_in"))
      (node (ref "IC8") (pin "3") (pinfunction "LT_3") (pintype "input"))
      (node (ref "IC8") (pin "4") (pinfunction "BI_4") (pintype "input"))
      (node (ref "JP1") (pin "1") (pinfunction "1_1") (pintype "passive"))
      (node (ref "S0") (pin "1") (pinfunction "S_1") (pintype "passive"))
      (node (ref "S0") (pin "2") (pinfunction "S1_2") (pintype "passive"))
      (node (ref "S1") (pin "1") (pinfunction "S_1") (pintype "passive"))
      (node (ref "S1") (pin "2") (pinfunction "S1_2") (pintype "passive"))
    )
    (net (code "104") (name "unconnected-(IC11A-6-Pad7)") (class "Default")
      (node (ref "IC11") (pin "7") (pinfunction "6_7") (pintype "output"))
    )
    (net (code "105") (name "unconnected-(IC11A-7-Pad8)") (class "Default")
      (node (ref "IC11") (pin "8") (pinfunction "7_8") (pintype "output"))
    )
    (net (code "106") (name "unconnected-(IC11A-8-Pad9)") (class "Default")
      (node (ref "IC11") (pin "9") (pinfunction "8_9") (pintype "output"))
    )
    (net (code "107") (name "unconnected-(IC11A-9-Pad10)") (class "Default")
      (node (ref "IC11") (pin "10") (pinfunction "9_10") (pintype "output"))
    )
    (net (code "108") (name "unconnected-(IC11A-10-Pad11)") (class "Default")
      (node (ref "IC11") (pin "11") (pinfunction "10_11") (pintype "output"))
    )
    (net (code "109") (name "unconnected-(IC11A-11-Pad13)") (class "Default")
      (node (ref "IC11") (pin "13") (pinfunction "11_13") (pintype "output"))
    )
    (net (code "110") (name "unconnected-(IC11A-12-Pad14)") (class "Default")
      (node (ref "IC11") (pin "14") (pinfunction "12_14") (pintype "output"))
    )
    (net (code "111") (name "unconnected-(IC11A-13-Pad15)") (class "Default")
      (node (ref "IC11") (pin "15") (pinfunction "13_15") (pintype "output"))
    )
    (net (code "112") (name "unconnected-(IC11A-14-Pad16)") (class "Default")
      (node (ref "IC11") (pin "16") (pinfunction "14_16") (pintype "output"))
    )
    (net (code "113") (name "unconnected-(IC11A-15-Pad17)") (class "Default")
      (node (ref "IC11") (pin "17") (pinfunction "15_17") (pintype "output"))
    )
  )
)
